# MGNGSQ4_Extender.net
KiCad netlist of a schematic drawn in Altium Designer
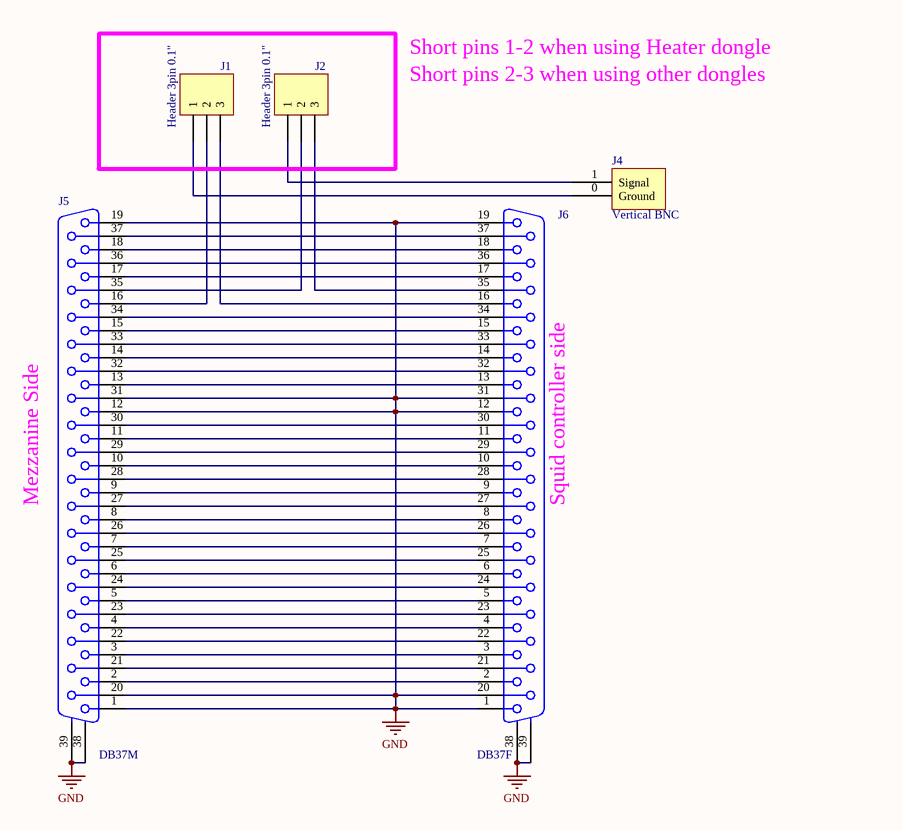
[diagram p0: MGNGSQ4_Extender.SchDoc]

(export (version "E")
  (design (tool "Eeschema 10.0.6"))
  (components
    (comp (ref "J1")
      (value "Header 3pin 0.1\"")
      (footprint "HDR1X3")
      (description "Header, 0.1\", 3-Pin straight")
      (fields (field (name "MANUFACTURER") "Digikey"))
      (libsource (lib "MGNGSQ4_Dongles") (part "Header3"))
    )
    (comp (ref "J2")
      (value "Header 3pin 0.1\"")
      (footprint "HDR1X3")
      (description "Header, 0.1\", 3-Pin straight")
      (fields (field (name "MANUFACTURER") "Digikey"))
      (libsource (lib "MGNGSQ4_Dongles") (part "Header3"))
    )
    (comp (ref "J4")
      (value "Vertical BNC")
      (footprint "BNCVert")
      (libsource (lib "MGNGSQ4_Dongles") (part "BNCVertical"))
    )
    (comp (ref "J5")
      (value "DB37M")
      (footprint "DSUB37-M")
      (libsource (lib "MGNGSQ4_Dongles") (part "DB37M"))
    )
    (comp (ref "J6")
      (value "DB37F")
      (footprint "DSUB37-F")
      (libsource (lib "MGNGSQ4_Dongles") (part "DB37F"))
    )
  )
  (nets
    (net (code "1") (name "GND") (class "Default")
      (node (ref "J5") (pin "1") (pinfunction "1_1") (pintype "passive"))
      (node (ref "J5") (pin "12") (pinfunction "12_12") (pintype "passive"))
      (node (ref "J5") (pin "19") (pinfunction "19_19") (pintype "passive"))
      (node (ref "J5") (pin "20") (pinfunction "20_20") (pintype "passive"))
      (node (ref "J5") (pin "31") (pinfunction "31_31") (pintype "passive"))
      (node (ref "J5") (pin "38") (pinfunction "MH1_38") (pintype "passive"))
      (node (ref "J5") (pin "39") (pinfunction "MH2_39") (pintype "passive"))
      (node (ref "J6") (pin "1") (pinfunction "1_1") (pintype "passive"))
      (node (ref "J6") (pin "12") (pinfunction "12_12") (pintype "passive"))
      (node (ref "J6") (pin "19") (pinfunction "19_19") (pintype "passive"))
      (node (ref "J6") (pin "20") (pinfunction "20_20") (pintype "passive"))
      (node (ref "J6") (pin "31") (pinfunction "31_31") (pintype "passive"))
      (node (ref "J6") (pin "38") (pinfunction "MH1_38") (pintype "passive"))
      (node (ref "J6") (pin "39") (pinfunction "MH2_39") (pintype "passive"))
    )
    (net (code "2") (name "Net-(J1-Pad2)") (class "Default")
      (node (ref "J1") (pin "2") (pinfunction "2_2") (pintype "passive"))
      (node (ref "J5") (pin "16") (pinfunction "16_16") (pintype "passive"))
    )
    (net (code "3") (name "Net-(J1-Pad3)") (class "Default")
      (node (ref "J1") (pin "3") (pinfunction "3_3") (pintype "passive"))
      (node (ref "J6") (pin "16") (pinfunction "16_16") (pintype "passive"))
    )
    (net (code "4") (name "Net-(J2-Pad2)") (class "Default")
      (node (ref "J2") (pin "2") (pinfunction "2_2") (pintype "passive"))
      (node (ref "J5") (pin "35") (pinfunction "35_35") (pintype "passive"))
    )
    (net (code "5") (name "Net-(J2-Pad3)") (class "Default")
      (node (ref "J2") (pin "3") (pinfunction "3_3") (pintype "passive"))
      (node (ref "J6") (pin "35") (pinfunction "35_35") (pintype "passive"))
    )
    (net (code "6") (name "Net-(J4-Ground)") (class "Default")
      (node (ref "J1") (pin "1") (pinfunction "1_1") (pintype "passive"))
      (node (ref "J4") (pin "0") (pinfunction "Ground_0") (pintype "passive"))
    )
    (net (code "7") (name "Net-(J4-Signal)") (class "Default")
      (node (ref "J2") (pin "1") (pinfunction "1_1") (pintype "passive"))
      (node (ref "J4") (pin "1") (pinfunction "Signal_1") (pintype "passive"))
    )
    (net (code "8") (name "Net-(J5-Pad2)") (class "Default")
      (node (ref "J5") (pin "2") (pinfunction "2_2") (pintype "passive"))
      (node (ref "J6") (pin "2") (pinfunction "2_2") (pintype "passive"))
    )
    (net (code "9") (name "Net-(J5-Pad3)") (class "Default")
      (node (ref "J5") (pin "3") (pinfunction "3_3") (pintype "passive"))
      (node (ref "J6") (pin "3") (pinfunction "3_3") (pintype "passive"))
    )
    (net (code "10") (name "Net-(J5-Pad4)") (class "Default")
      (node (ref "J5") (pin "4") (pinfunction "4_4") (pintype "passive"))
      (node (ref "J6") (pin "4") (pinfunction "4_4") (pintype "passive"))
    )
    (net (code "11") (name "Net-(J5-Pad5)") (class "Default")
      (node (ref "J5") (pin "5") (pinfunction "5_5") (pintype "passive"))
      (node (ref "J6") (pin "5") (pinfunction "5_5") (pintype "passive"))
    )
    (net (code "12") (name "Net-(J5-Pad6)") (class "Default")
      (node (ref "J5") (pin "6") (pinfunction "6_6") (pintype "passive"))
      (node (ref "J6") (pin "6") (pinfunction "6_6") (pintype "passive"))
    )
    (net (code "13") (name "Net-(J5-Pad7)") (class "Default")
      (node (ref "J5") (pin "7") (pinfunction "7_7") (pintype "passive"))
      (node (ref "J6") (pin "7") (pinfunction "7_7") (pintype "passive"))
    )
    (net (code "14") (name "Net-(J5-Pad8)") (class "Default")
      (node (ref "J5") (pin "8") (pinfunction "8_8") (pintype "passive"))
      (node (ref "J6") (pin "8") (pinfunction "8_8") (pintype "passive"))
    )
    (net (code "15") (name "Net-(J5-Pad9)") (class "Default")
      (node (ref "J5") (pin "9") (pinfunction "9_9") (pintype "passive"))
      (node (ref "J6") (pin "9") (pinfunction "9_9") (pintype "passive"))
    )
    (net (code "16") (name "Net-(J5-Pad10)") (class "Default")
      (node (ref "J5") (pin "10") (pinfunction "10_10") (pintype "passive"))
      (node (ref "J6") (pin "10") (pinfunction "10_10") (pintype "passive"))
    )
    (net (code "17") (name "Net-(J5-Pad11)") (class "Default")
      (node (ref "J5") (pin "11") (pinfunction "11_11") (pintype "passive"))
      (node (ref "J6") (pin "11") (pinfunction "11_11") (pintype "passive"))
    )
    (net (code "18") (name "Net-(J5-Pad13)") (class "Default")
      (node (ref "J5") (pin "13") (pinfunction "13_13") (pintype "passive"))
      (node (ref "J6") (pin "13") (pinfunction "13_13") (pintype "passive"))
    )
    (net (code "19") (name "Net-(J5-Pad14)") (class "Default")
      (node (ref "J5") (pin "14") (pinfunction "14_14") (pintype "passive"))
      (node (ref "J6") (pin "14") (pinfunction "14_14") (pintype "passive"))
    )
    (net (code "20") (name "Net-(J5-Pad15)") (class "Default")
      (node (ref "J5") (pin "15") (pinfunction "15_15") (pintype "passive"))
      (node (ref "J6") (pin "15") (pinfunction "15_15") (pintype "passive"))
    )
    (net (code "21") (name "Net-(J5-Pad17)") (class "Default")
      (node (ref "J5") (pin "17") (pinfunction "17_17") (pintype "passive"))
      (node (ref "J6") (pin "17") (pinfunction "17_17") (pintype "passive"))
    )
    (net (code "22") (name "Net-(J5-Pad18)") (class "Default")
      (node (ref "J5") (pin "18") (pinfunction "18_18") (pintype "passive"))
      (node (ref "J6") (pin "18") (pinfunction "18_18") (pintype "passive"))
    )
    (net (code "23") (name "Net-(J5-Pad21)") (class "Default")
      (node (ref "J5") (pin "21") (pinfunction "21_21") (pintype "passive"))
      (node (ref "J6") (pin "21") (pinfunction "21_21") (pintype "passive"))
    )
    (net (code "24") (name "Net-(J5-Pad22)") (class "Default")
      (node (ref "J5") (pin "22") (pinfunction "22_22") (pintype "passive"))
      (node (ref "J6") (pin "22") (pinfunction "22_22") (pintype "passive"))
    )
    (net (code "25") (name "Net-(J5-Pad23)") (class "Default")
      (node (ref "J5") (pin "23") (pinfunction "23_23") (pintype "passive"))
      (node (ref "J6") (pin "23") (pinfunction "23_23") (pintype "passive"))
    )
    (net (code "26") (name "Net-(J5-Pad24)") (class "Default")
      (node (ref "J5") (pin "24") (pinfunction "24_24") (pintype "passive"))
      (node (ref "J6") (pin "24") (pinfunction "24_24") (pintype "passive"))
    )
    (net (code "27") (name "Net-(J5-Pad25)") (class "Default")
      (node (ref "J5") (pin "25") (pinfunction "25_25") (pintype "passive"))
      (node (ref "J6") (pin "25") (pinfunction "25_25") (pintype "passive"))
    )
    (net (code "28") (name "Net-(J5-Pad26)") (class "Default")
      (node (ref "J5") (pin "26") (pinfunction "26_26") (pintype "passive"))
      (node (ref "J6") (pin "26") (pinfunction "26_26") (pintype "passive"))
    )
    (net (code "29") (name "Net-(J5-Pad27)") (class "Default")
      (node (ref "J5") (pin "27") (pinfunction "27_27") (pintype "passive"))
      (node (ref "J6") (pin "27") (pinfunction "27_27") (pintype "passive"))
    )
    (net (code "30") (name "Net-(J5-Pad28)") (class "Default")
      (node (ref "J5") (pin "28") (pinfunction "28_28") (pintype "passive"))
      (node (ref "J6") (pin "28") (pinfunction "28_28") (pintype "passive"))
    )
    (net (code "31") (name "Net-(J5-Pad29)") (class "Default")
      (node (ref "J5") (pin "29") (pinfunction "29_29") (pintype "passive"))
      (node (ref "J6") (pin "29") (pinfunction "29_29") (pintype "passive"))
    )
    (net (code "32") (name "Net-(J5-Pad30)") (class "Default")
      (node (ref "J5") (pin "30") (pinfunction "30_30") (pintype "passive"))
      (node (ref "J6") (pin "30") (pinfunction "30_30") (pintype "passive"))
    )
    (net (code "33") (name "Net-(J5-Pad32)") (class "Default")
      (node (ref "J5") (pin "32") (pinfunction "32_32") (pintype "passive"))
      (node (ref "J6") (pin "32") (pinfunction "32_32") (pintype "passive"))
    )
    (net (code "34") (name "Net-(J5-Pad33)") (class "Default")
      (node (ref "J5") (pin "33") (pinfunction "33_33") (pintype "passive"))
      (node (ref "J6") (pin "33") (pinfunction "33_33") (pintype "passive"))
    )
    (net (code "35") (name "Net-(J5-Pad34)") (class "Default")
      (node (ref "J5") (pin "34") (pinfunction "34_34") (pintype "passive"))
      (node (ref "J6") (pin "34") (pinfunction "34_34") (pintype "passive"))
    )
    (net (code "36") (name "Net-(J5-Pad36)") (class "Default")
      (node (ref "J5") (pin "36") (pinfunction "36_36") (pintype "passive"))
      (node (ref "J6") (pin "36") (pinfunction "36_36") (pintype "passive"))
    )
    (net (code "37") (name "Net-(J5-Pad37)") (class "Default")
      (node (ref "J5") (pin "37") (pinfunction "37_37") (pintype "passive"))
      (node (ref "J6") (pin "37") (pinfunction "37_37") (pintype "passive"))
    )
  )
)
